# 02MCU.net
KiCad netlist of a schematic drawn in Altium Designer
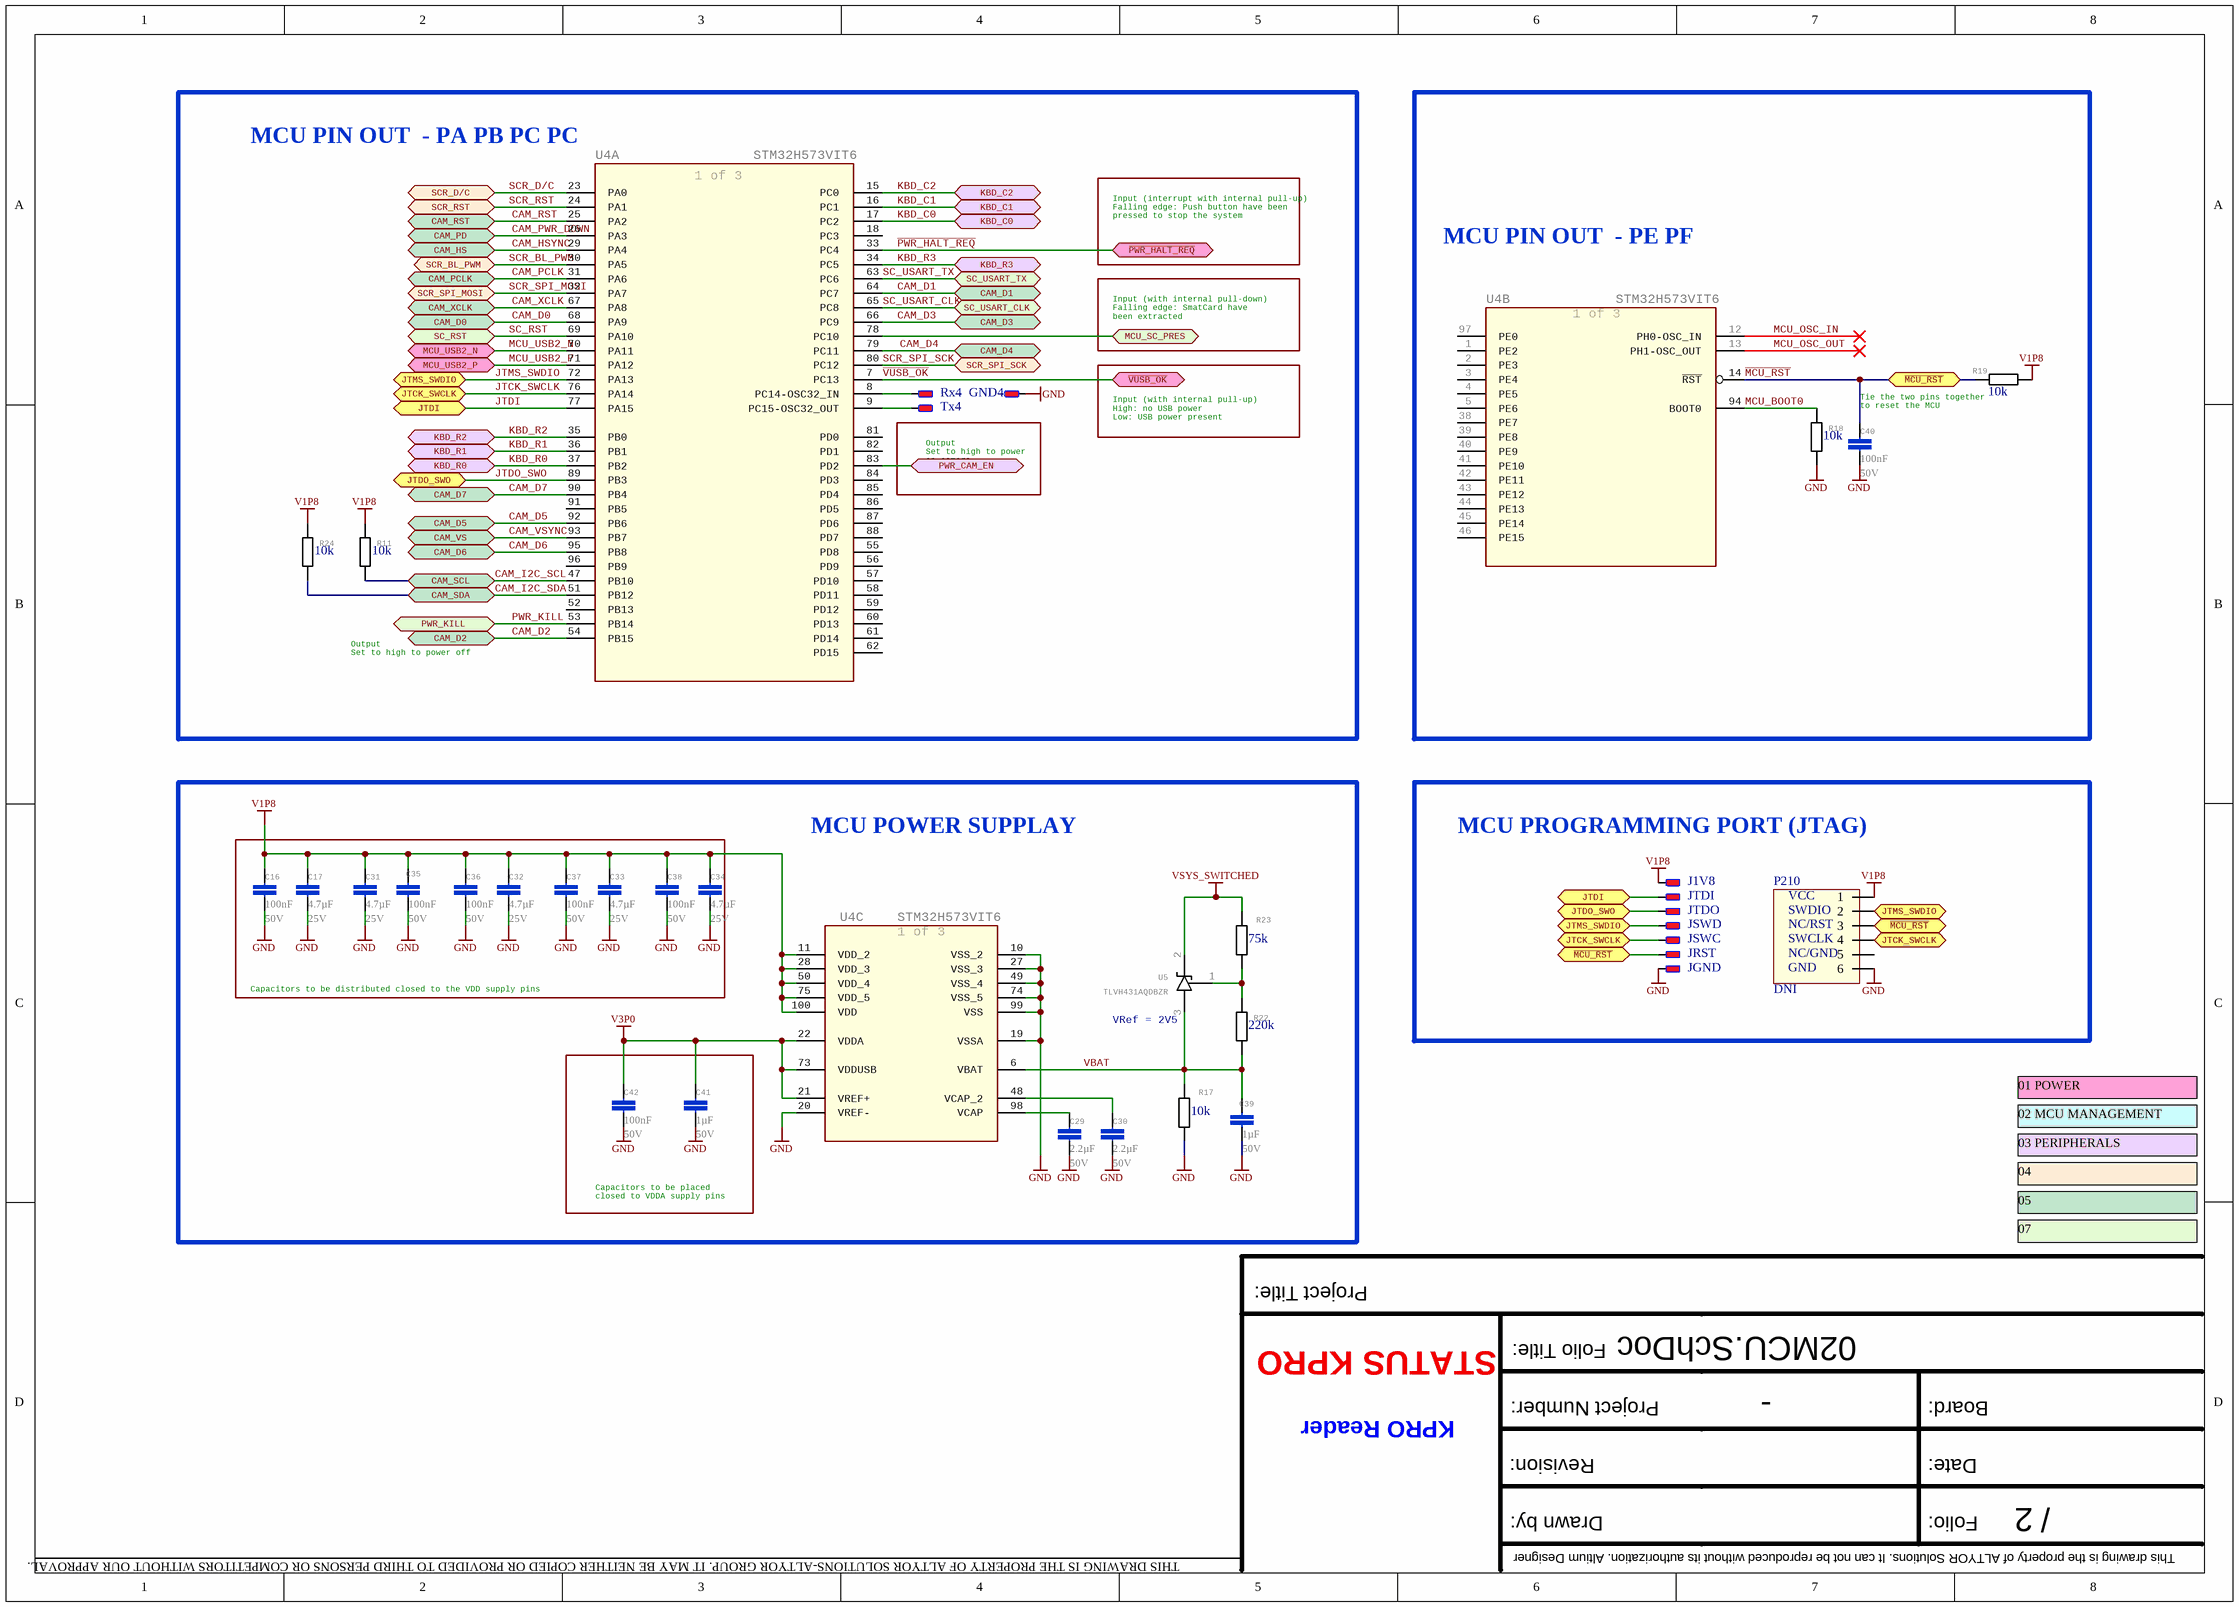
[diagram p0: 02MCU.SchDoc]

(export (version "E")
  (design (tool "Eeschema 10.0.6"))
  (components
    (comp (ref "C16")
      (value "0402B104K500CT")
      (footprint "0402 - CAPACITOR")
      (description "CAP X7R 100nF 50V ±10% 0402")
      (fields
        (field (name "MANUFACTURER") "WALSIN")
        (field (name "VOLTAGE") "50V")
        (field (name "NAME") "100nF")
      )
      (libsource (lib "KCP-2282-600") (part "C-EU-C100NF-X7R-16V-0402"))
    )
    (comp (ref "C17")
      (value "0805X475M250CT")
      (footprint "0805 - CAPACITOR")
      (description "CAP X5R 4.7µF 25V ±10% 0805")
      (fields
        (field (name "MANUFACTURER") "WALSIN")
        (field (name "VOLTAGE") "25V")
        (field (name "NAME") "4.7µF")
      )
      (libsource (lib "KCP-2282-600") (part "C-EU-C4.7µF-X5R-6.3V-0805"))
    )
    (comp (ref "C29")
      (value "805X225M500CT")
      (footprint "0805 - CAPACITOR")
      (description "CAP X5R 2.2µF 50V ±10% 0805")
      (fields
        (field (name "MANUFACTURER") "WALSIN")
        (field (name "VOLTAGE") "50V")
        (field (name "NAME") "2.2µF")
      )
      (libsource (lib "KCP-2282-600") (part "C-EU-C2,2µF-X7R-16V-0805"))
    )
    (comp (ref "C30")
      (value "805X225M500CT")
      (footprint "0805 - CAPACITOR")
      (description "CAP X5R 2.2µF 50V ±10% 0805")
      (fields
        (field (name "MANUFACTURER") "WALSIN")
        (field (name "VOLTAGE") "50V")
        (field (name "NAME") "2.2µF")
      )
      (libsource (lib "KCP-2282-600") (part "C-EU-C2,2µF-X7R-16V-0805"))
    )
    (comp (ref "C31")
      (value "0805X475M250CT")
      (footprint "0805 - CAPACITOR")
      (description "CAP X5R 4.7µF 25V ±10% 0805")
      (fields
        (field (name "MANUFACTURER") "WALSIN")
        (field (name "VOLTAGE") "25V")
        (field (name "NAME") "4.7µF")
      )
      (libsource (lib "KCP-2282-600") (part "C-EU-C4.7µF-X5R-6.3V-0805"))
    )
    (comp (ref "C32")
      (value "0805X475M250CT")
      (footprint "0805 - CAPACITOR")
      (description "CAP X5R 4.7µF 25V ±10% 0805")
      (fields
        (field (name "MANUFACTURER") "WALSIN")
        (field (name "VOLTAGE") "25V")
        (field (name "NAME") "4.7µF")
      )
      (libsource (lib "KCP-2282-600") (part "C-EU-C4.7µF-X5R-6.3V-0805"))
    )
    (comp (ref "C33")
      (value "0805X475M250CT")
      (footprint "0805 - CAPACITOR")
      (description "CAP X5R 4.7µF 25V ±10% 0805")
      (fields
        (field (name "MANUFACTURER") "WALSIN")
        (field (name "VOLTAGE") "25V")
        (field (name "NAME") "4.7µF")
      )
      (libsource (lib "KCP-2282-600") (part "C-EU-C4.7µF-X5R-6.3V-0805"))
    )
    (comp (ref "C34")
      (value "0805X475M250CT")
      (footprint "0805 - CAPACITOR")
      (description "CAP X5R 4.7µF 25V ±10% 0805")
      (fields
        (field (name "MANUFACTURER") "WALSIN")
        (field (name "VOLTAGE") "25V")
        (field (name "NAME") "4.7µF")
      )
      (libsource (lib "KCP-2282-600") (part "C-EU-C4.7µF-X5R-6.3V-0805"))
    )
    (comp (ref "C35")
      (value "0402B104K500CT")
      (footprint "0402 - CAPACITOR")
      (description "CAP X7R 100nF 50V ±10% 0402")
      (fields
        (field (name "MANUFACTURER") "WALSIN")
        (field (name "VOLTAGE") "50V")
        (field (name "NAME") "100nF")
      )
      (libsource (lib "KCP-2282-600") (part "C-EU-C100NF-X7R-16V-0402"))
    )
    (comp (ref "C36")
      (value "0402B104K500CT")
      (footprint "0402 - CAPACITOR")
      (description "CAP X7R 100nF 50V ±10% 0402")
      (fields
        (field (name "MANUFACTURER") "WALSIN")
        (field (name "VOLTAGE") "50V")
        (field (name "NAME") "100nF")
      )
      (libsource (lib "KCP-2282-600") (part "C-EU-C100NF-X7R-16V-0402"))
    )
    (comp (ref "C37")
      (value "0402B104K500CT")
      (footprint "0402 - CAPACITOR")
      (description "CAP X7R 100nF 50V ±10% 0402")
      (fields
        (field (name "MANUFACTURER") "WALSIN")
        (field (name "VOLTAGE") "50V")
        (field (name "NAME") "100nF")
      )
      (libsource (lib "KCP-2282-600") (part "C-EU-C100NF-X7R-16V-0402"))
    )
    (comp (ref "C38")
      (value "0402B104K500CT")
      (footprint "0402 - CAPACITOR")
      (description "CAP X7R 100nF 50V ±10% 0402")
      (fields
        (field (name "MANUFACTURER") "WALSIN")
        (field (name "VOLTAGE") "50V")
        (field (name "NAME") "100nF")
      )
      (libsource (lib "KCP-2282-600") (part "C-EU-C100NF-X7R-16V-0402"))
    )
    (comp (ref "C39")
      (value "0603X105K500CT")
      (footprint "0603 - CAPACITOR")
      (description "CAP X5R 1µF 50V ±10% 0603")
      (fields
        (field (name "MANUFACTURER") "WALSIN")
        (field (name "VOLTAGE") "50V")
        (field (name "NAME") "1µF")
      )
      (libsource (lib "KCP-2282-600") (part "C-EU-C1µF-X5R-6.3V-0603"))
    )
    (comp (ref "C40")
      (value "0402B104K500CT")
      (footprint "0402 - CAPACITOR")
      (description "CAP X7R 100nF 50V ±10% 0402")
      (fields
        (field (name "MANUFACTURER") "WALSIN")
        (field (name "VOLTAGE") "50V")
        (field (name "NAME") "100nF")
      )
      (libsource (lib "KCP-2282-600") (part "C-EU-C100NF-X7R-16V-0402"))
    )
    (comp (ref "C41")
      (value "0603X105K500CT")
      (footprint "0603 - CAPACITOR")
      (description "CAP X5R 1µF 50V ±10% 0603")
      (fields
        (field (name "MANUFACTURER") "WALSIN")
        (field (name "VOLTAGE") "50V")
        (field (name "NAME") "1µF")
      )
      (libsource (lib "") (part "C-EU-C1µF-X5R-6.3V-0603_1"))
    )
    (comp (ref "C42")
      (value "0402B104K500CT")
      (footprint "0402 - CAPACITOR")
      (description "CAP X7R 100nF 50V ±10% 0402")
      (fields
        (field (name "MANUFACTURER") "WALSIN")
        (field (name "VOLTAGE") "50V")
        (field (name "NAME") "100nF")
      )
      (libsource (lib "KCP-2282-600") (part "C-EU-C100NF-X7R-16V-0402"))
    )
    (comp (ref "GND4")
      (value "TP")
      (footprint "TESTPOINT 1MM")
      (description "Pointe de test 1.27mm")
      (libsource (lib "KCP-2282-600") (part "TP"))
    )
    (comp (ref "J1V8")
      (value "TP")
      (footprint "TESTPOINT 1MM")
      (description "Pointe de test 1.27mm")
      (libsource (lib "KCP-2282-600") (part "TP"))
    )
    (comp (ref "JGND")
      (value "TP")
      (footprint "TESTPOINT 1MM")
      (description "Pointe de test 1.27mm")
      (libsource (lib "KCP-2282-600") (part "TP"))
    )
    (comp (ref "JRST")
      (value "TP")
      (footprint "TESTPOINT 1MM")
      (description "Pointe de test 1.27mm")
      (libsource (lib "KCP-2282-600") (part "TP"))
    )
    (comp (ref "JSWC")
      (value "TP")
      (footprint "TESTPOINT 1MM")
      (description "Pointe de test 1.27mm")
      (libsource (lib "KCP-2282-600") (part "TP"))
    )
    (comp (ref "JSWD")
      (value "TP")
      (footprint "TESTPOINT 1MM")
      (description "Pointe de test 1.27mm")
      (libsource (lib "KCP-2282-600") (part "TP"))
    )
    (comp (ref "JTDI")
      (value "TP")
      (footprint "TESTPOINT 1MM")
      (description "Pointe de test 1.27mm")
      (libsource (lib "KCP-2282-600") (part "TP"))
    )
    (comp (ref "JTDO")
      (value "TP")
      (footprint "TESTPOINT 1MM")
      (description "Pointe de test 1.27mm")
      (libsource (lib "KCP-2282-600") (part "TP"))
    )
    (comp (ref "P210")
      (value "TC2030-MCP-NL")
      (footprint "TC2030-MCP-NL-BOT")
      (description "Connecteur Tag Connect - 6pts RJ45")
      (fields (field (name "NAME") "DNI") (field (name "MANUFACTURER") "TAG CONNECT"))
      (libsource (lib "DbLibAltium") (part "TC2030"))
    )
    (comp (ref "R11")
      (value "RC0402FR-0710KL")
      (footprint "0402 - RESISTOR")
      (description "RES 10k 63mW 1% 0402")
      (fields (field (name "MANUFACTURER") "YAGEO") (field (name "NAME") "10k"))
      (libsource (lib "KCP-2282-600") (part "R-EU-R10K-1%-0402"))
    )
    (comp (ref "R17")
      (value "RC0402FR-0710KL")
      (footprint "0402 - RESISTOR")
      (description "RES 10k 63mW 1% 0402")
      (fields (field (name "MANUFACTURER") "YAGEO") (field (name "NAME") "10k"))
      (libsource (lib "KCP-2282-600") (part "R-EU-R10K-1%-0402"))
    )
    (comp (ref "R18")
      (value "RC0402FR-0710KL")
      (footprint "0402 - RESISTOR")
      (description "RES 10k 63mW 1% 0402")
      (fields (field (name "MANUFACTURER") "YAGEO") (field (name "NAME") "10k"))
      (libsource (lib "KCP-2282-600") (part "R-EU-R10K-1%-0402"))
    )
    (comp (ref "R19")
      (value "RC0402FR-0710KL")
      (footprint "0402 - RESISTOR")
      (description "RES 10k 63mW 1% 0402")
      (fields (field (name "MANUFACTURER") "YAGEO") (field (name "NAME") "10k"))
      (libsource (lib "KCP-2282-600") (part "R-EU-R10K-1%-0402"))
    )
    (comp (ref "R22")
      (value "RC0402FR-07220KL")
      (footprint "0402 - RESISTOR")
      (description "RES 220k 63mW 1% 0402")
      (fields (field (name "MANUFACTURER") "YAGEO") (field (name "NAME") "220k"))
      (libsource (lib "KCP-2282-600") (part "R-EU-R220K-1%-0402"))
    )
    (comp (ref "R23")
      (value "RC0402FR-0775KL")
      (footprint "0402 - RESISTOR")
      (description "RES 75k 63mW 1% 0402")
      (fields (field (name "MANUFACTURER") "YAGEO") (field (name "NAME") "75k"))
      (libsource (lib "KCP-2282-600") (part "R-EU-R75K-1%-0402"))
    )
    (comp (ref "R24")
      (value "RC0402FR-0710KL")
      (footprint "0402 - RESISTOR")
      (description "RES 10k 63mW 1% 0402")
      (fields (field (name "MANUFACTURER") "YAGEO") (field (name "NAME") "10k"))
      (libsource (lib "KCP-2282-600") (part "R-EU-R10K-1%-0402"))
    )
    (comp (ref "Rx4")
      (value "TP")
      (footprint "TESTPOINT 1MM")
      (description "Pointe de test 1.27mm")
      (libsource (lib "KCP-2282-600") (part "TP"))
    )
    (comp (ref "Tx4")
      (value "TP")
      (footprint "TESTPOINT 1MM")
      (description "Pointe de test 1.27mm")
      (libsource (lib "KCP-2282-600") (part "TP"))
    )
    (comp (ref "U4")
      (value "STM32H573VIT6")
      (footprint "LQFP-100")
      (fields (field (name "1OF3") "1 of 3") (field (name "MANUFACTURER") "STMicroelectronics"))
      (libsource (lib "") (part "STM32H573VIT6_1"))
    )
    (comp (ref "U5")
      (value "TLVH431AQDBZR")
      (footprint "SOT23-VAR AB")
      (description "Low voltage adjustable 1.5% precision shunt regulators, SOT23")
      (fields (field (name "MANUFACTURER") "TEXAS"))
      (libsource (lib "KCP-2282-600") (part "TLVH431AQDBZR"))
    )
  )
  (nets
    (net (code "1") (name "/CAM_D0") (class "Default")
      (node (ref "U4") (pin "68") (pinfunction "PA9_68") (pintype "passive"))
    )
    (net (code "2") (name "/CAM_D1") (class "Default")
      (node (ref "U4") (pin "64") (pinfunction "PC7_64") (pintype "passive"))
    )
    (net (code "3") (name "/CAM_D2") (class "Default")
      (node (ref "U4") (pin "54") (pinfunction "PB15_54") (pintype "passive"))
    )
    (net (code "4") (name "/CAM_D3") (class "Default")
      (node (ref "U4") (pin "66") (pinfunction "PC9_66") (pintype "passive"))
    )
    (net (code "5") (name "/CAM_D4") (class "Default")
      (node (ref "U4") (pin "79") (pinfunction "PC11_79") (pintype "passive"))
    )
    (net (code "6") (name "/CAM_D5") (class "Default")
      (node (ref "U4") (pin "92") (pinfunction "PB6_92") (pintype "passive"))
    )
    (net (code "7") (name "/CAM_D6") (class "Default")
      (node (ref "U4") (pin "95") (pinfunction "PB8_95") (pintype "passive"))
    )
    (net (code "8") (name "/CAM_D7") (class "Default")
      (node (ref "U4") (pin "90") (pinfunction "PB4_90") (pintype "passive"))
    )
    (net (code "9") (name "/CAM_HSYNC") (class "Default")
      (node (ref "U4") (pin "29") (pinfunction "PA4_29") (pintype "passive"))
    )
    (net (code "10") (name "/CAM_I2C_SCL") (class "Default")
      (node (ref "R11") (pin "1") (pinfunction "1_1") (pintype "passive"))
      (node (ref "U4") (pin "47") (pinfunction "PB10_47") (pintype "passive"))
    )
    (net (code "11") (name "/CAM_I2C_SDA") (class "Default")
      (node (ref "R24") (pin "1") (pinfunction "1_1") (pintype "passive"))
      (node (ref "U4") (pin "51") (pinfunction "PB12_51") (pintype "passive"))
    )
    (net (code "12") (name "/CAM_PCLK") (class "Default")
      (node (ref "U4") (pin "31") (pinfunction "PA6_31") (pintype "passive"))
    )
    (net (code "13") (name "/CAM_PWR_DOWN") (class "Default")
      (node (ref "U4") (pin "26") (pinfunction "PA3_26") (pintype "passive"))
    )
    (net (code "14") (name "/CAM_RST") (class "Default")
      (node (ref "U4") (pin "25") (pinfunction "PA2_25") (pintype "passive"))
    )
    (net (code "15") (name "/CAM_VSYNC") (class "Default")
      (node (ref "U4") (pin "93") (pinfunction "PB7_93") (pintype "passive"))
    )
    (net (code "16") (name "/CAM_XCLK") (class "Default")
      (node (ref "U4") (pin "67") (pinfunction "PA8_67") (pintype "passive"))
    )
    (net (code "17") (name "/JTCK_SWCLK") (class "Default")
      (node (ref "JSWC") (pin "1") (pinfunction "PT_1") (pintype "passive"))
      (node (ref "P210") (pin "4") (pinfunction "4_4") (pintype "passive"))
      (node (ref "U4") (pin "76") (pinfunction "PA14_76") (pintype "passive"))
    )
    (net (code "18") (name "/JTDI") (class "Default")
      (node (ref "JTDI") (pin "1") (pinfunction "PT_1") (pintype "passive"))
      (node (ref "U4") (pin "77") (pinfunction "PA15_77") (pintype "passive"))
    )
    (net (code "19") (name "/JTDO_SWO") (class "Default")
      (node (ref "JTDO") (pin "1") (pinfunction "PT_1") (pintype "passive"))
      (node (ref "U4") (pin "89") (pinfunction "PB3_89") (pintype "passive"))
    )
    (net (code "20") (name "/JTMS_SWDIO") (class "Default")
      (node (ref "JSWD") (pin "1") (pinfunction "PT_1") (pintype "passive"))
      (node (ref "P210") (pin "2") (pinfunction "2_2") (pintype "passive"))
      (node (ref "U4") (pin "72") (pinfunction "PA13_72") (pintype "passive"))
    )
    (net (code "21") (name "/KBD_C0") (class "Default")
      (node (ref "U4") (pin "17") (pinfunction "PC2_17") (pintype "passive"))
    )
    (net (code "22") (name "/KBD_C1") (class "Default")
      (node (ref "U4") (pin "16") (pinfunction "PC1_16") (pintype "passive"))
    )
    (net (code "23") (name "/KBD_C2") (class "Default")
      (node (ref "U4") (pin "15") (pinfunction "PC0_15") (pintype "passive"))
    )
    (net (code "24") (name "/KBD_R0") (class "Default")
      (node (ref "U4") (pin "37") (pinfunction "PB2_37") (pintype "passive"))
    )
    (net (code "25") (name "/KBD_R1") (class "Default")
      (node (ref "U4") (pin "36") (pinfunction "PB1_36") (pintype "passive"))
    )
    (net (code "26") (name "/KBD_R2") (class "Default")
      (node (ref "U4") (pin "35") (pinfunction "PB0_35") (pintype "passive"))
    )
    (net (code "27") (name "/KBD_R3") (class "Default")
      (node (ref "U4") (pin "34") (pinfunction "PC5_34") (pintype "passive"))
    )
    (net (code "28") (name "/MCU_BOOT0") (class "Default")
      (node (ref "R18") (pin "2") (pinfunction "2_2") (pintype "passive"))
      (node (ref "U4") (pin "94") (pinfunction "BOOT0_94") (pintype "passive"))
    )
    (net (code "29") (name "/MCU_OSC_IN") (class "Default")
      (node (ref "U4") (pin "12") (pinfunction "PH0-OSC_IN_12") (pintype "passive+no_connect"))
    )
    (net (code "30") (name "/MCU_OSC_OUT") (class "Default")
      (node (ref "U4") (pin "13") (pinfunction "PH1-OSC_OUT_13") (pintype "passive+no_connect"))
    )
    (net (code "31") (name "/MCU_SC_PRES") (class "Default")
      (node (ref "U4") (pin "78") (pinfunction "PC10_78") (pintype "passive"))
    )
    (net (code "32") (name "/MCU_USB2_N") (class "Default")
      (node (ref "U4") (pin "70") (pinfunction "PA11_70") (pintype "passive"))
    )
    (net (code "33") (name "/MCU_USB2_P") (class "Default")
      (node (ref "U4") (pin "71") (pinfunction "PA12_71") (pintype "passive"))
    )
    (net (code "34") (name "/PWR_CAM_EN") (class "Default")
      (node (ref "U4") (pin "83") (pinfunction "PD2_83") (pintype "passive"))
    )
    (net (code "35") (name "/PWR_KILL") (class "Default")
      (node (ref "U4") (pin "53") (pinfunction "PB14_53") (pintype "passive"))
    )
    (net (code "36") (name "/SCR_BL_PWM") (class "Default")
      (node (ref "U4") (pin "30") (pinfunction "PA5_30") (pintype "passive"))
    )
    (net (code "37") (name "/SCR_D{slash}C") (class "Default")
      (node (ref "U4") (pin "23") (pinfunction "PA0_23") (pintype "passive"))
    )
    (net (code "38") (name "/SCR_RST") (class "Default")
      (node (ref "U4") (pin "24") (pinfunction "PA1_24") (pintype "passive"))
    )
    (net (code "39") (name "/SCR_SPI_MOSI") (class "Default")
      (node (ref "U4") (pin "32") (pinfunction "PA7_32") (pintype "passive"))
    )
    (net (code "40") (name "/SCR_SPI_SCK") (class "Default")
      (node (ref "U4") (pin "80") (pinfunction "PC12_80") (pintype "passive"))
    )
    (net (code "41") (name "/SC_RST") (class "Default")
      (node (ref "U4") (pin "69") (pinfunction "PA10_69") (pintype "passive"))
    )
    (net (code "42") (name "/SC_USART_CLK") (class "Default")
      (node (ref "U4") (pin "65") (pinfunction "PC8_65") (pintype "passive"))
    )
    (net (code "43") (name "/SC_USART_TX") (class "Default")
      (node (ref "U4") (pin "63") (pinfunction "PC6_63") (pintype "passive"))
    )
    (net (code "44") (name "/VBAT") (class "Default")
      (node (ref "C39") (pin "1") (pinfunction "1_1") (pintype "passive"))
      (node (ref "R17") (pin "2") (pinfunction "2_2") (pintype "passive"))
      (node (ref "R22") (pin "1") (pinfunction "1_1") (pintype "passive"))
      (node (ref "U4") (pin "6") (pinfunction "VBAT_6") (pintype "passive"))
      (node (ref "U5") (pin "3") (pinfunction "A_3") (pintype "passive"))
    )
    (net (code "45") (name "/~{MCU_RST}") (class "Default")
      (node (ref "C40") (pin "1") (pinfunction "1_1") (pintype "passive"))
      (node (ref "JRST") (pin "1") (pinfunction "PT_1") (pintype "passive"))
      (node (ref "P210") (pin "3") (pinfunction "3_3") (pintype "passive"))
      (node (ref "R19") (pin "1") (pinfunction "1_1") (pintype "passive"))
      (node (ref "U4") (pin "14") (pinfunction "~{RST}_14") (pintype "passive"))
    )
    (net (code "46") (name "/~{PWR_HALT_REQ}") (class "Default")
      (node (ref "U4") (pin "33") (pinfunction "PC4_33") (pintype "passive"))
    )
    (net (code "47") (name "/~{VUSB_OK}") (class "Default")
      (node (ref "U4") (pin "7") (pinfunction "PC13_7") (pintype "passive"))
    )
    (net (code "48") (name "GND") (class "Default")
      (node (ref "C16") (pin "2") (pinfunction "2_2") (pintype "passive"))
      (node (ref "C17") (pin "2") (pinfunction "2_2") (pintype "passive"))
      (node (ref "C29") (pin "2") (pinfunction "2_2") (pintype "passive"))
      (node (ref "C30") (pin "2") (pinfunction "2_2") (pintype "passive"))
      (node (ref "C31") (pin "2") (pinfunction "2_2") (pintype "passive"))
      (node (ref "C32") (pin "2") (pinfunction "2_2") (pintype "passive"))
      (node (ref "C33") (pin "2") (pinfunction "2_2") (pintype "passive"))
      (node (ref "C34") (pin "2") (pinfunction "2_2") (pintype "passive"))
      (node (ref "C35") (pin "2") (pinfunction "2_2") (pintype "passive"))
      (node (ref "C36") (pin "2") (pinfunction "2_2") (pintype "passive"))
      (node (ref "C37") (pin "2") (pinfunction "2_2") (pintype "passive"))
      (node (ref "C38") (pin "2") (pinfunction "2_2") (pintype "passive"))
      (node (ref "C39") (pin "2") (pinfunction "2_2") (pintype "passive"))
      (node (ref "C40") (pin "2") (pinfunction "2_2") (pintype "passive"))
      (node (ref "C41") (pin "2") (pinfunction "2_2") (pintype "passive"))
      (node (ref "C42") (pin "2") (pinfunction "2_2") (pintype "passive"))
      (node (ref "GND4") (pin "1") (pinfunction "PT_1") (pintype "passive"))
      (node (ref "JGND") (pin "1") (pinfunction "PT_1") (pintype "passive"))
      (node (ref "P210") (pin "6") (pinfunction "6_6") (pintype "passive"))
      (node (ref "R17") (pin "1") (pinfunction "1_1") (pintype "passive"))
      (node (ref "R18") (pin "1") (pinfunction "1_1") (pintype "passive"))
      (node (ref "U4") (pin "10") (pinfunction "VSS_2_10") (pintype "passive"))
      (node (ref "U4") (pin "19") (pinfunction "VSSA_19") (pintype "passive"))
      (node (ref "U4") (pin "20") (pinfunction "VREF-_20") (pintype "passive"))
      (node (ref "U4") (pin "27") (pinfunction "VSS_3_27") (pintype "passive"))
      (node (ref "U4") (pin "49") (pinfunction "VSS_4_49") (pintype "passive"))
      (node (ref "U4") (pin "74") (pinfunction "VSS_5_74") (pintype "passive"))
      (node (ref "U4") (pin "99") (pinfunction "VSS_99") (pintype "passive"))
    )
    (net (code "49") (name "Net-(Rx4-PT)") (class "Default")
      (node (ref "Rx4") (pin "1") (pinfunction "PT_1") (pintype "passive"))
      (node (ref "U4") (pin "8") (pinfunction "PC14-OSC32_IN_8") (pintype "passive"))
    )
    (net (code "50") (name "Net-(Tx4-PT)") (class "Default")
      (node (ref "Tx4") (pin "1") (pinfunction "PT_1") (pintype "passive"))
      (node (ref "U4") (pin "9") (pinfunction "PC15-OSC32_OUT_9") (pintype "passive"))
    )
    (net (code "51") (name "Net-(U4C-VCAP)") (class "Default")
      (node (ref "C29") (pin "1") (pinfunction "1_1") (pintype "passive"))
      (node (ref "U4") (pin "98") (pinfunction "VCAP_98") (pintype "passive"))
    )
    (net (code "52") (name "Net-(U4C-VCAP_2)") (class "Default")
      (node (ref "C30") (pin "1") (pinfunction "1_1") (pintype "passive"))
      (node (ref "U4") (pin "48") (pinfunction "VCAP_2_48") (pintype "passive"))
    )
    (net (code "53") (name "Net-(U5-REF)") (class "Default")
      (node (ref "R22") (pin "2") (pinfunction "2_2") (pintype "passive"))
      (node (ref "R23") (pin "1") (pinfunction "1_1") (pintype "passive"))
      (node (ref "U5") (pin "1") (pinfunction "REF_1") (pintype "passive"))
    )
    (net (code "54") (name "V1P8") (class "Default")
      (node (ref "C16") (pin "1") (pinfunction "1_1") (pintype "passive"))
      (node (ref "C17") (pin "1") (pinfunction "1_1") (pintype "passive"))
      (node (ref "C31") (pin "1") (pinfunction "1_1") (pintype "passive"))
      (node (ref "C32") (pin "1") (pinfunction "1_1") (pintype "passive"))
      (node (ref "C33") (pin "1") (pinfunction "1_1") (pintype "passive"))
      (node (ref "C34") (pin "1") (pinfunction "1_1") (pintype "passive"))
      (node (ref "C35") (pin "1") (pinfunction "1_1") (pintype "passive"))
      (node (ref "C36") (pin "1") (pinfunction "1_1") (pintype "passive"))
      (node (ref "C37") (pin "1") (pinfunction "1_1") (pintype "passive"))
      (node (ref "C38") (pin "1") (pinfunction "1_1") (pintype "passive"))
      (node (ref "J1V8") (pin "1") (pinfunction "PT_1") (pintype "passive"))
      (node (ref "P210") (pin "1") (pinfunction "1_1") (pintype "passive"))
      (node (ref "R11") (pin "2") (pinfunction "2_2") (pintype "passive"))
      (node (ref "R19") (pin "2") (pinfunction "2_2") (pintype "passive"))
      (node (ref "R24") (pin "2") (pinfunction "2_2") (pintype "passive"))
      (node (ref "U4") (pin "100") (pinfunction "VDD_100") (pintype "passive"))
      (node (ref "U4") (pin "11") (pinfunction "VDD_2_11") (pintype "passive"))
      (node (ref "U4") (pin "28") (pinfunction "VDD_3_28") (pintype "passive"))
      (node (ref "U4") (pin "50") (pinfunction "VDD_4_50") (pintype "passive"))
      (node (ref "U4") (pin "75") (pinfunction "VDD_5_75") (pintype "passive"))
    )
    (net (code "55") (name "V3P0") (class "Default")
      (node (ref "C41") (pin "1") (pinfunction "1_1") (pintype "passive"))
      (node (ref "C42") (pin "1") (pinfunction "1_1") (pintype "passive"))
      (node (ref "U4") (pin "21") (pinfunction "VREF+_21") (pintype "passive"))
      (node (ref "U4") (pin "22") (pinfunction "VDDA_22") (pintype "passive"))
      (node (ref "U4") (pin "73") (pinfunction "VDDUSB_73") (pintype "passive"))
    )
    (net (code "56") (name "VSYS_SWITCHED") (class "Default")
      (node (ref "R23") (pin "2") (pinfunction "2_2") (pintype "passive"))
      (node (ref "U5") (pin "2") (pinfunction "K_2") (pintype "passive"))
    )
    (net (code "57") (name "unconnected-(P210-Pad5)") (class "Default")
      (node (ref "P210") (pin "5") (pinfunction "5_5") (pintype "passive"))
    )
    (net (code "58") (name "unconnected-(U4A-PB5-Pad91)") (class "Default")
      (node (ref "U4") (pin "91") (pinfunction "PB5_91") (pintype "passive"))
    )
    (net (code "59") (name "unconnected-(U4A-PB9-Pad96)") (class "Default")
      (node (ref "U4") (pin "96") (pinfunction "PB9_96") (pintype "passive"))
    )
    (net (code "60") (name "unconnected-(U4A-PB13-Pad52)") (class "Default")
      (node (ref "U4") (pin "52") (pinfunction "PB13_52") (pintype "passive"))
    )
    (net (code "61") (name "unconnected-(U4A-PC3-Pad18)") (class "Default")
      (node (ref "U4") (pin "18") (pinfunction "PC3_18") (pintype "passive"))
    )
    (net (code "62") (name "unconnected-(U4A-PD0-Pad81)") (class "Default")
      (node (ref "U4") (pin "81") (pinfunction "PD0_81") (pintype "passive"))
    )
    (net (code "63") (name "unconnected-(U4A-PD1-Pad82)") (class "Default")
      (node (ref "U4") (pin "82") (pinfunction "PD1_82") (pintype "passive"))
    )
    (net (code "64") (name "unconnected-(U4A-PD3-Pad84)") (class "Default")
      (node (ref "U4") (pin "84") (pinfunction "PD3_84") (pintype "passive"))
    )
    (net (code "65") (name "unconnected-(U4A-PD4-Pad85)") (class "Default")
      (node (ref "U4") (pin "85") (pinfunction "PD4_85") (pintype "passive"))
    )
    (net (code "66") (name "unconnected-(U4A-PD5-Pad86)") (class "Default")
      (node (ref "U4") (pin "86") (pinfunction "PD5_86") (pintype "passive"))
    )
    (net (code "67") (name "unconnected-(U4A-PD6-Pad87)") (class "Default")
      (node (ref "U4") (pin "87") (pinfunction "PD6_87") (pintype "passive"))
    )
    (net (code "68") (name "unconnected-(U4A-PD7-Pad88)") (class "Default")
      (node (ref "U4") (pin "88") (pinfunction "PD7_88") (pintype "passive"))
    )
    (net (code "69") (name "unconnected-(U4A-PD8-Pad55)") (class "Default")
      (node (ref "U4") (pin "55") (pinfunction "PD8_55") (pintype "passive"))
    )
    (net (code "70") (name "unconnected-(U4A-PD9-Pad56)") (class "Default")
      (node (ref "U4") (pin "56") (pinfunction "PD9_56") (pintype "passive"))
    )
    (net (code "71") (name "unconnected-(U4A-PD10-Pad57)") (class "Default")
      (node (ref "U4") (pin "57") (pinfunction "PD10_57") (pintype "passive"))
    )
    (net (code "72") (name "unconnected-(U4A-PD11-Pad58)") (class "Default")
      (node (ref "U4") (pin "58") (pinfunction "PD11_58") (pintype "passive"))
    )
    (net (code "73") (name "unconnected-(U4A-PD12-Pad59)") (class "Default")
      (node (ref "U4") (pin "59") (pinfunction "PD12_59") (pintype "passive"))
    )
    (net (code "74") (name "unconnected-(U4A-PD13-Pad60)") (class "Default")
      (node (ref "U4") (pin "60") (pinfunction "PD13_60") (pintype "passive"))
    )
    (net (code "75") (name "unconnected-(U4A-PD14-Pad61)") (class "Default")
      (node (ref "U4") (pin "61") (pinfunction "PD14_61") (pintype "passive"))
    )
    (net (code "76") (name "unconnected-(U4A-PD15-Pad62)") (class "Default")
      (node (ref "U4") (pin "62") (pinfunction "PD15_62") (pintype "passive"))
    )
    (net (code "77") (name "unconnected-(U4B-PE0-Pad97)") (class "Default")
      (node (ref "U4") (pin "97") (pinfunction "PE0_97") (pintype "passive"))
    )
    (net (code "78") (name "unconnected-(U4B-PE2-Pad1)") (class "Default")
      (node (ref "U4") (pin "1") (pinfunction "PE2_1") (pintype "passive"))
    )
    (net (code "79") (name "unconnected-(U4B-PE3-Pad2)") (class "Default")
      (node (ref "U4") (pin "2") (pinfunction "PE3_2") (pintype "passive"))
    )
    (net (code "80") (name "unconnected-(U4B-PE4-Pad3)") (class "Default")
      (node (ref "U4") (pin "3") (pinfunction "PE4_3") (pintype "passive"))
    )
    (net (code "81") (name "unconnected-(U4B-PE5-Pad4)") (class "Default")
      (node (ref "U4") (pin "4") (pinfunction "PE5_4") (pintype "passive"))
    )
    (net (code "82") (name "unconnected-(U4B-PE6-Pad5)") (class "Default")
      (node (ref "U4") (pin "5") (pinfunction "PE6_5") (pintype "passive"))
    )
    (net (code "83") (name "unconnected-(U4B-PE7-Pad38)") (class "Default")
      (node (ref "U4") (pin "38") (pinfunction "PE7_38") (pintype "passive"))
    )
    (net (code "84") (name "unconnected-(U4B-PE8-Pad39)") (class "Default")
      (node (ref "U4") (pin "39") (pinfunction "PE8_39") (pintype "passive"))
    )
    (net (code "85") (name "unconnected-(U4B-PE9-Pad40)") (class "Default")
      (node (ref "U4") (pin "40") (pinfunction "PE9_40") (pintype "passive"))
    )
    (net (code "86") (name "unconnected-(U4B-PE10-Pad41)") (class "Default")
      (node (ref "U4") (pin "41") (pinfunction "PE10_41") (pintype "passive"))
    )
    (net (code "87") (name "unconnected-(U4B-PE11-Pad42)") (class "Default")
      (node (ref "U4") (pin "42") (pinfunction "PE11_42") (pintype "passive"))
    )
    (net (code "88") (name "unconnected-(U4B-PE12-Pad43)") (class "Default")
      (node (ref "U4") (pin "43") (pinfunction "PE12_43") (pintype "passive"))
    )
    (net (code "89") (name "unconnected-(U4B-PE13-Pad44)") (class "Default")
      (node (ref "U4") (pin "44") (pinfunction "PE13_44") (pintype "passive"))
    )
    (net (code "90") (name "unconnected-(U4B-PE14-Pad45)") (class "Default")
      (node (ref "U4") (pin "45") (pinfunction "PE14_45") (pintype "passive"))
    )
    (net (code "91") (name "unconnected-(U4B-PE15-Pad46)") (class "Default")
      (node (ref "U4") (pin "46") (pinfunction "PE15_46") (pintype "passive"))
    )
  )
)
